# Power.net
KiCad netlist of a schematic drawn in Altium Designer
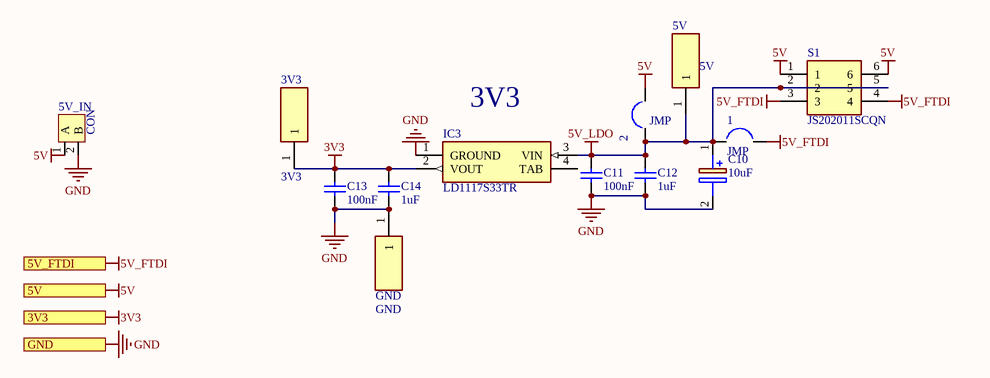
[diagram p0: Power.SchDoc]

(export (version "E")
  (design (tool "Eeschema 10.0.6"))
  (components
    (comp (ref "1") (value "JMP") (footprint "Jumper") (libsource (lib "SamacSys") (part "JMP")))
    (comp (ref "2") (value "JMP") (footprint "Jumper") (libsource (lib "SamacSys") (part "JMP")))
    (comp (ref "3V3")
      (value "3V3")
      (footprint "1508000150000030")
      (description "Undefined or Miscellaneous")
      (fields (field (name "MANUFACTURER_PART_NUMBER") "5015") (field (name "MOUSER PART NUMBER") "534-5015"))
      (libsource (lib "") (part "5015_1"))
    )
    (comp (ref "5V")
      (value "5V")
      (footprint "1508000150000030")
      (description "Undefined or Miscellaneous")
      (fields (field (name "MANUFACTURER_PART_NUMBER") "5015") (field (name "MOUSER PART NUMBER") "534-5015"))
      (libsource (lib "") (part "5015_1"))
    )
    (comp (ref "5V_IN") (value "CON") (footprint "TBG-5.0") (libsource (lib "SamacSys") (part "CON")))
    (comp (ref "C10")
      (value "10uF")
      (footprint "CAPPM3216X180N")
      (description "Capacitor Polarised")
      (fields
        (field (name "MANUFACTURER_PART_NUMBER") "TAJA106K004RNJ")
        (field (name "MOUSER PART NUMBER") "581-TAJA106K004R")
      )
      (libsource (lib "*") (part "TAJA106K004RNJ"))
    )
    (comp (ref "C11")
      (value "100nF")
      (footprint "1608[0603]")
      (description "Capacitor")
      (fields (field (name "PUBLISHER") "Altium Limited"))
      (libsource (lib "Miscellaneous Devices") (part "Cap Semi"))
    )
    (comp (ref "C12")
      (value "1uF")
      (footprint "1608[0603]")
      (description "Capacitor")
      (fields (field (name "PUBLISHER") "Altium Limited"))
      (libsource (lib "Miscellaneous Devices") (part "Cap Semi"))
    )
    (comp (ref "C13")
      (value "100nF")
      (footprint "1608[0603]")
      (description "Capacitor")
      (fields (field (name "PUBLISHER") "Altium Limited"))
      (libsource (lib "Miscellaneous Devices") (part "Cap Semi"))
    )
    (comp (ref "C14")
      (value "1uF")
      (footprint "1608[0603]")
      (description "Capacitor")
      (fields (field (name "PUBLISHER") "Altium Limited"))
      (libsource (lib "Miscellaneous Devices") (part "Cap Semi"))
    )
    (comp (ref "GND")
      (value "GND")
      (footprint "1508000150000030")
      (description "Undefined or Miscellaneous")
      (fields (field (name "MANUFACTURER_PART_NUMBER") "5015") (field (name "MOUSER PART NUMBER") "534-5015"))
      (libsource (lib "*") (part "5015"))
    )
    (comp (ref "IC3")
      (value "LD1117S33TR")
      (footprint "SOT230P700X180-4N")
      (description "Integrated Circuit")
      (fields (field (name "MOUSER PART NUMBER") "511-LD1117S33") (field (name "RS PART NUMBER") "7140697P"))
      (libsource (lib "*") (part "LD1117S33TR"))
    )
    (comp (ref "S1")
      (value "JS202011SCQN")
      (footprint "SamacSys:JS202011SCQN")
      (description "Switch")
      (fields (field (name "MOUSER PART NUMBER") "611-JS202011SCQN"))
      (libsource (lib "*") (part "JS202011SCQN"))
    )
  )
  (nets
    (net (code "1") (name "3V3") (class "Default")
      (node (ref "3V3") (pin "1") (pinfunction "1_1") (pintype "passive"))
      (node (ref "C13") (pin "1") (pinfunction "1_1") (pintype "passive"))
      (node (ref "C14") (pin "1") (pinfunction "1_1") (pintype "passive"))
      (node (ref "IC3") (pin "2") (pinfunction "VOUT_2") (pintype "output"))
    )
    (net (code "2") (name "5V") (class "Default")
      (node (ref "2") (pin "2") (pinfunction "2_2") (pintype "passive"))
      (node (ref "5V_IN") (pin "1") (pinfunction "A_1") (pintype "passive"))
      (node (ref "S1") (pin "1") (pinfunction "1_1") (pintype "passive"))
      (node (ref "S1") (pin "6") (pinfunction "6_6") (pintype "passive"))
    )
    (net (code "3") (name "5V_FTDI") (class "Default")
      (node (ref "1") (pin "2") (pinfunction "2_2") (pintype "passive"))
      (node (ref "S1") (pin "3") (pinfunction "3_3") (pintype "passive"))
      (node (ref "S1") (pin "4") (pinfunction "4_4") (pintype "passive"))
    )
    (net (code "4") (name "5V_LDO") (class "Default")
      (node (ref "1") (pin "1") (pinfunction "1_1") (pintype "passive"))
      (node (ref "2") (pin "1") (pinfunction "1_1") (pintype "passive"))
      (node (ref "5V") (pin "1") (pinfunction "1_1") (pintype "passive"))
      (node (ref "C10") (pin "1") (pinfunction "+_1") (pintype "passive"))
      (node (ref "C11") (pin "1") (pinfunction "1_1") (pintype "passive"))
      (node (ref "C12") (pin "1") (pinfunction "1_1") (pintype "passive"))
      (node (ref "IC3") (pin "3") (pinfunction "VIN_3") (pintype "input"))
      (node (ref "S1") (pin "2") (pinfunction "2_2") (pintype "passive"))
      (node (ref "S1") (pin "5") (pinfunction "5_5") (pintype "passive"))
    )
    (net (code "5") (name "GND") (class "Default")
      (node (ref "5V_IN") (pin "2") (pinfunction "B_2") (pintype "passive"))
      (node (ref "C10") (pin "2") (pinfunction "-_2") (pintype "passive"))
      (node (ref "C11") (pin "2") (pinfunction "2_2") (pintype "passive"))
      (node (ref "C12") (pin "2") (pinfunction "2_2") (pintype "passive"))
      (node (ref "C13") (pin "2") (pinfunction "2_2") (pintype "passive"))
      (node (ref "C14") (pin "2") (pinfunction "2_2") (pintype "passive"))
      (node (ref "GND") (pin "1") (pinfunction "1_1") (pintype "passive"))
      (node (ref "IC3") (pin "1") (pinfunction "GROUND_1") (pintype "passive"))
    )
    (net (code "6") (name "unconnected-(IC3-TAB-Pad4)") (class "Default")
      (node (ref "IC3") (pin "4") (pinfunction "TAB_4") (pintype "passive"))
    )
  )
)
